# Communication.net
KiCad netlist of a schematic drawn in Altium Designer
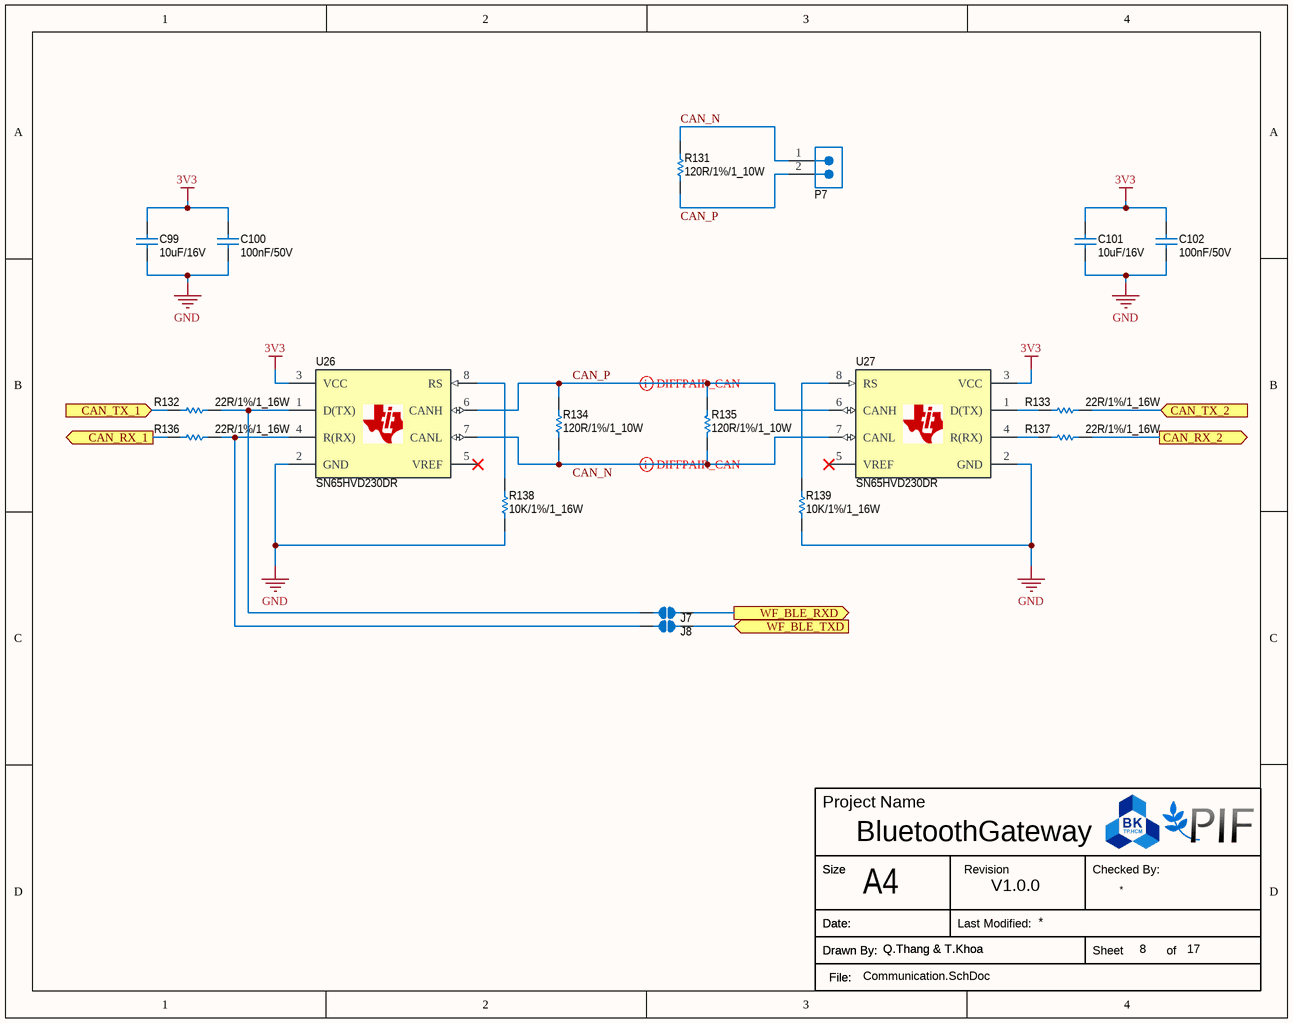
[diagram p0: Communication.SchDoc]

(export (version "E")
  (design (tool "Eeschema 10.0.6"))
  (components
    (comp (ref "C99")
      (value "10uF/16V")
      (footprint "CAP_0603")
      (description "CAP, size 0603, 10uF, 16V")
      (fields (field (name "SUPPLY PART NUMBER") "Tụ Gốm 0603 10uF 16V"))
      (libsource (lib "BluetoothTracking") (part "Ceramic_Cap_10uF_16V_0603"))
    )
    (comp (ref "C100")
      (value "100nF/50V")
      (footprint "CAP_0603")
      (description "CAP, size 0603, 100nF, 50V")
      (fields (field (name "SUPPLY PART NUMBER") "Tụ Gốm 0603 100nF (0.1uF) 50V"))
      (libsource (lib "BluetoothTracking") (part "Ceramic_Cap_100nF_50V_0603"))
    )
    (comp (ref "C101")
      (value "10uF/16V")
      (footprint "CAP_0603")
      (description "CAP, size 0603, 10uF, 16V")
      (fields (field (name "SUPPLY PART NUMBER") "Tụ Gốm 0603 10uF 16V"))
      (libsource (lib "BluetoothTracking") (part "Ceramic_Cap_10uF_16V_0603"))
    )
    (comp (ref "C102")
      (value "100nF/50V")
      (footprint "CAP_0603")
      (description "CAP, size 0603, 100nF, 50V")
      (fields (field (name "SUPPLY PART NUMBER") "Tụ Gốm 0603 100nF (0.1uF) 50V"))
      (libsource (lib "BluetoothTracking") (part "Ceramic_Cap_100nF_50V_0603"))
    )
    (comp (ref "J7")
      (value "Jumper_Open")
      (footprint "SolderBridgeOpen")
      (libsource (lib "BluetoothTracking") (part "Jumper_Open"))
    )
    (comp (ref "J8")
      (value "Jumper_Open")
      (footprint "SolderBridgeOpen")
      (libsource (lib "BluetoothTracking") (part "Jumper_Open"))
    )
    (comp (ref "P7")
      (value "3.81mm_2P")
      (footprint "Terminal_Block_3.81mm_2P")
      (description "Terminal Block THT, pitch 3.81mm, 2p, 300V, 10A")
      (fields
        (field (name "SUPPLY PART NUMBER") "UL-3.81-2-R Terminal Block Plug-in Hàn PCB 2 Chân Cong 3.81mm 300V 10A ULO")
      )
      (libsource (lib "BluetoothTracking") (part "Terminal_Block_3.81mm_2P"))
    )
    (comp (ref "R131")
      (value "120R/1%/1_10W")
      (footprint "Resistor_0603")
      (description "Resistor 0603 120 Ohm 1% 1_10W")
      (fields (field (name "SUPPLY PART NUMBER") "Điện Trở 120 Ohm 0603 1%"))
      (libsource (lib "BluetoothTracking") (part "Res_120R_0603_1%"))
    )
    (comp (ref "R132")
      (value "22R/1%/1_16W")
      (footprint "RESISTOR_0402")
      (description "Resistor 0402 22 Ohm 1% 1_16W")
      (libsource (lib "BluetoothTracking") (part "Res_22R_0402_1%"))
    )
    (comp (ref "R133")
      (value "22R/1%/1_16W")
      (footprint "RESISTOR_0402")
      (description "Resistor 0402 22 Ohm 1% 1_16W")
      (libsource (lib "BluetoothTracking") (part "Res_22R_0402_1%"))
    )
    (comp (ref "R134")
      (value "120R/1%/1_10W")
      (footprint "Resistor_0603")
      (description "Resistor 0603 120 Ohm 1% 1_10W")
      (fields (field (name "SUPPLY PART NUMBER") "Điện Trở 120 Ohm 0603 1%"))
      (libsource (lib "BluetoothTracking") (part "Res_120R_0603_1%"))
    )
    (comp (ref "R135")
      (value "120R/1%/1_10W")
      (footprint "Resistor_0603")
      (description "Resistor 0603 120 Ohm 1% 1_10W")
      (fields (field (name "SUPPLY PART NUMBER") "Điện Trở 120 Ohm 0603 1%"))
      (libsource (lib "BluetoothTracking") (part "Res_120R_0603_1%"))
    )
    (comp (ref "R136")
      (value "22R/1%/1_16W")
      (footprint "RESISTOR_0402")
      (description "Resistor 0402 22 Ohm 1% 1_16W")
      (libsource (lib "BluetoothTracking") (part "Res_22R_0402_1%"))
    )
    (comp (ref "R137")
      (value "22R/1%/1_16W")
      (footprint "RESISTOR_0402")
      (description "Resistor 0402 22 Ohm 1% 1_16W")
      (libsource (lib "BluetoothTracking") (part "Res_22R_0402_1%"))
    )
    (comp (ref "R138")
      (value "10K/1%/1_16W")
      (footprint "RESISTOR_0402")
      (description "Resistor 0402 10KOhm 1% 1_16W")
      (fields (field (name "SUPPLY PART NUMBER") "Điện Trở 10 KOhm 0402 1%"))
      (libsource (lib "BluetoothTracking") (part "Res_10K_0402_1%"))
    )
    (comp (ref "R139")
      (value "10K/1%/1_16W")
      (footprint "RESISTOR_0402")
      (description "Resistor 0402 10KOhm 1% 1_16W")
      (fields (field (name "SUPPLY PART NUMBER") "Điện Trở 10 KOhm 0402 1%"))
      (libsource (lib "BluetoothTracking") (part "Res_10K_0402_1%"))
    )
    (comp (ref "U26")
      (value "SN65HVD230DR")
      (footprint "SOIC-8")
      (description "1/1 Transceiver Half CANbus")
      (fields (field (name "SUPPLY PART NUMBER") "SN65HVD230DR CAN Transceiver 8-SOIC"))
      (libsource (lib "") (part "SN65HVD230DR_1"))
    )
    (comp (ref "U27")
      (value "SN65HVD230DR")
      (footprint "SOIC-8")
      (description "1/1 Transceiver Half CANbus")
      (fields (field (name "SUPPLY PART NUMBER") "SN65HVD230DR CAN Transceiver 8-SOIC"))
      (libsource (lib "BluetoothTracking") (part "SN65HVD230DR"))
    )
  )
  (nets
    (net (code "1") (name "/CAN_N") (class "Default")
      (node (ref "P7") (pin "1") (pinfunction "1_1") (pintype "passive"))
      (node (ref "R131") (pin "2") (pinfunction "2_2") (pintype "passive"))
      (node (ref "R134") (pin "1") (pinfunction "1_1") (pintype "passive"))
      (node (ref "R135") (pin "2") (pinfunction "2_2") (pintype "passive"))
      (node (ref "U26") (pin "7") (pinfunction "CANL_7") (pintype "bidirectional"))
      (node (ref "U27") (pin "7") (pinfunction "CANL_7") (pintype "bidirectional"))
    )
    (net (code "2") (name "/CAN_P") (class "Default")
      (node (ref "P7") (pin "2") (pinfunction "2_2") (pintype "passive"))
      (node (ref "R131") (pin "1") (pinfunction "1_1") (pintype "passive"))
      (node (ref "R134") (pin "2") (pinfunction "2_2") (pintype "passive"))
      (node (ref "R135") (pin "1") (pinfunction "1_1") (pintype "passive"))
      (node (ref "U26") (pin "6") (pinfunction "CANH_6") (pintype "bidirectional"))
      (node (ref "U27") (pin "6") (pinfunction "CANH_6") (pintype "bidirectional"))
    )
    (net (code "3") (name "/CAN_RX_1") (class "Default")
      (node (ref "R136") (pin "1") (pinfunction "1_1") (pintype "passive"))
    )
    (net (code "4") (name "/CAN_RX_2") (class "Default")
      (node (ref "R137") (pin "2") (pinfunction "2_2") (pintype "passive"))
    )
    (net (code "5") (name "/CAN_TX_1") (class "Default")
      (node (ref "R132") (pin "1") (pinfunction "1_1") (pintype "passive"))
    )
    (net (code "6") (name "/CAN_TX_2") (class "Default")
      (node (ref "R133") (pin "2") (pinfunction "2_2") (pintype "passive"))
    )
    (net (code "7") (name "/WF_BLE_RXD") (class "Default")
      (node (ref "J7") (pin "2") (pinfunction "2_2") (pintype "passive"))
    )
    (net (code "8") (name "/WF_BLE_TXD") (class "Default")
      (node (ref "J8") (pin "2") (pinfunction "2_2") (pintype "passive"))
    )
    (net (code "9") (name "3V3") (class "Default")
      (node (ref "C100") (pin "2") (pinfunction "2_2") (pintype "passive"))
      (node (ref "C101") (pin "2") (pinfunction "2_2") (pintype "passive"))
      (node (ref "C102") (pin "2") (pinfunction "2_2") (pintype "passive"))
      (node (ref "C99") (pin "2") (pinfunction "2_2") (pintype "passive"))
      (node (ref "U26") (pin "3") (pinfunction "VCC_3") (pintype "power_in"))
      (node (ref "U27") (pin "3") (pinfunction "VCC_3") (pintype "power_in"))
    )
    (net (code "10") (name "GND") (class "Default")
      (node (ref "C100") (pin "1") (pinfunction "1_1") (pintype "passive"))
      (node (ref "C101") (pin "1") (pinfunction "1_1") (pintype "passive"))
      (node (ref "C102") (pin "1") (pinfunction "1_1") (pintype "passive"))
      (node (ref "C99") (pin "1") (pinfunction "1_1") (pintype "passive"))
      (node (ref "R138") (pin "2") (pinfunction "2_2") (pintype "passive"))
      (node (ref "R139") (pin "2") (pinfunction "2_2") (pintype "passive"))
      (node (ref "U26") (pin "2") (pinfunction "GND_2") (pintype "power_in"))
      (node (ref "U27") (pin "2") (pinfunction "GND_2") (pintype "power_in"))
    )
    (net (code "11") (name "Net-(U26-D(TX))") (class "Default")
      (node (ref "J7") (pin "1") (pinfunction "1_1") (pintype "passive"))
      (node (ref "R132") (pin "2") (pinfunction "2_2") (pintype "passive"))
      (node (ref "U26") (pin "1") (pinfunction "D(TX)_1") (pintype "passive"))
    )
    (net (code "12") (name "Net-(U26-R(RX))") (class "Default")
      (node (ref "J8") (pin "1") (pinfunction "1_1") (pintype "passive"))
      (node (ref "R136") (pin "2") (pinfunction "2_2") (pintype "passive"))
      (node (ref "U26") (pin "4") (pinfunction "R(RX)_4") (pintype "passive"))
    )
    (net (code "13") (name "Net-(U26-RS)") (class "Default")
      (node (ref "R138") (pin "1") (pinfunction "1_1") (pintype "passive"))
      (node (ref "U26") (pin "8") (pinfunction "RS_8") (pintype "input"))
    )
    (net (code "14") (name "Net-(U27-D(TX))") (class "Default")
      (node (ref "R133") (pin "1") (pinfunction "1_1") (pintype "passive"))
      (node (ref "U27") (pin "1") (pinfunction "D(TX)_1") (pintype "passive"))
    )
    (net (code "15") (name "Net-(U27-R(RX))") (class "Default")
      (node (ref "R137") (pin "1") (pinfunction "1_1") (pintype "passive"))
      (node (ref "U27") (pin "4") (pinfunction "R(RX)_4") (pintype "passive"))
    )
    (net (code "16") (name "Net-(U27-RS)") (class "Default")
      (node (ref "R139") (pin "1") (pinfunction "1_1") (pintype "passive"))
      (node (ref "U27") (pin "8") (pinfunction "RS_8") (pintype "input"))
    )
    (net (code "17") (name "unconnected-(U26-VREF-Pad5)") (class "Default")
      (node (ref "U26") (pin "5") (pinfunction "VREF_5") (pintype "power_in+no_connect"))
    )
    (net (code "18") (name "unconnected-(U27-VREF-Pad5)") (class "Default")
      (node (ref "U27") (pin "5") (pinfunction "VREF_5") (pintype "power_in+no_connect"))
    )
  )
)
